# Sheet1.net
KiCad netlist of a schematic drawn in Altium Designer
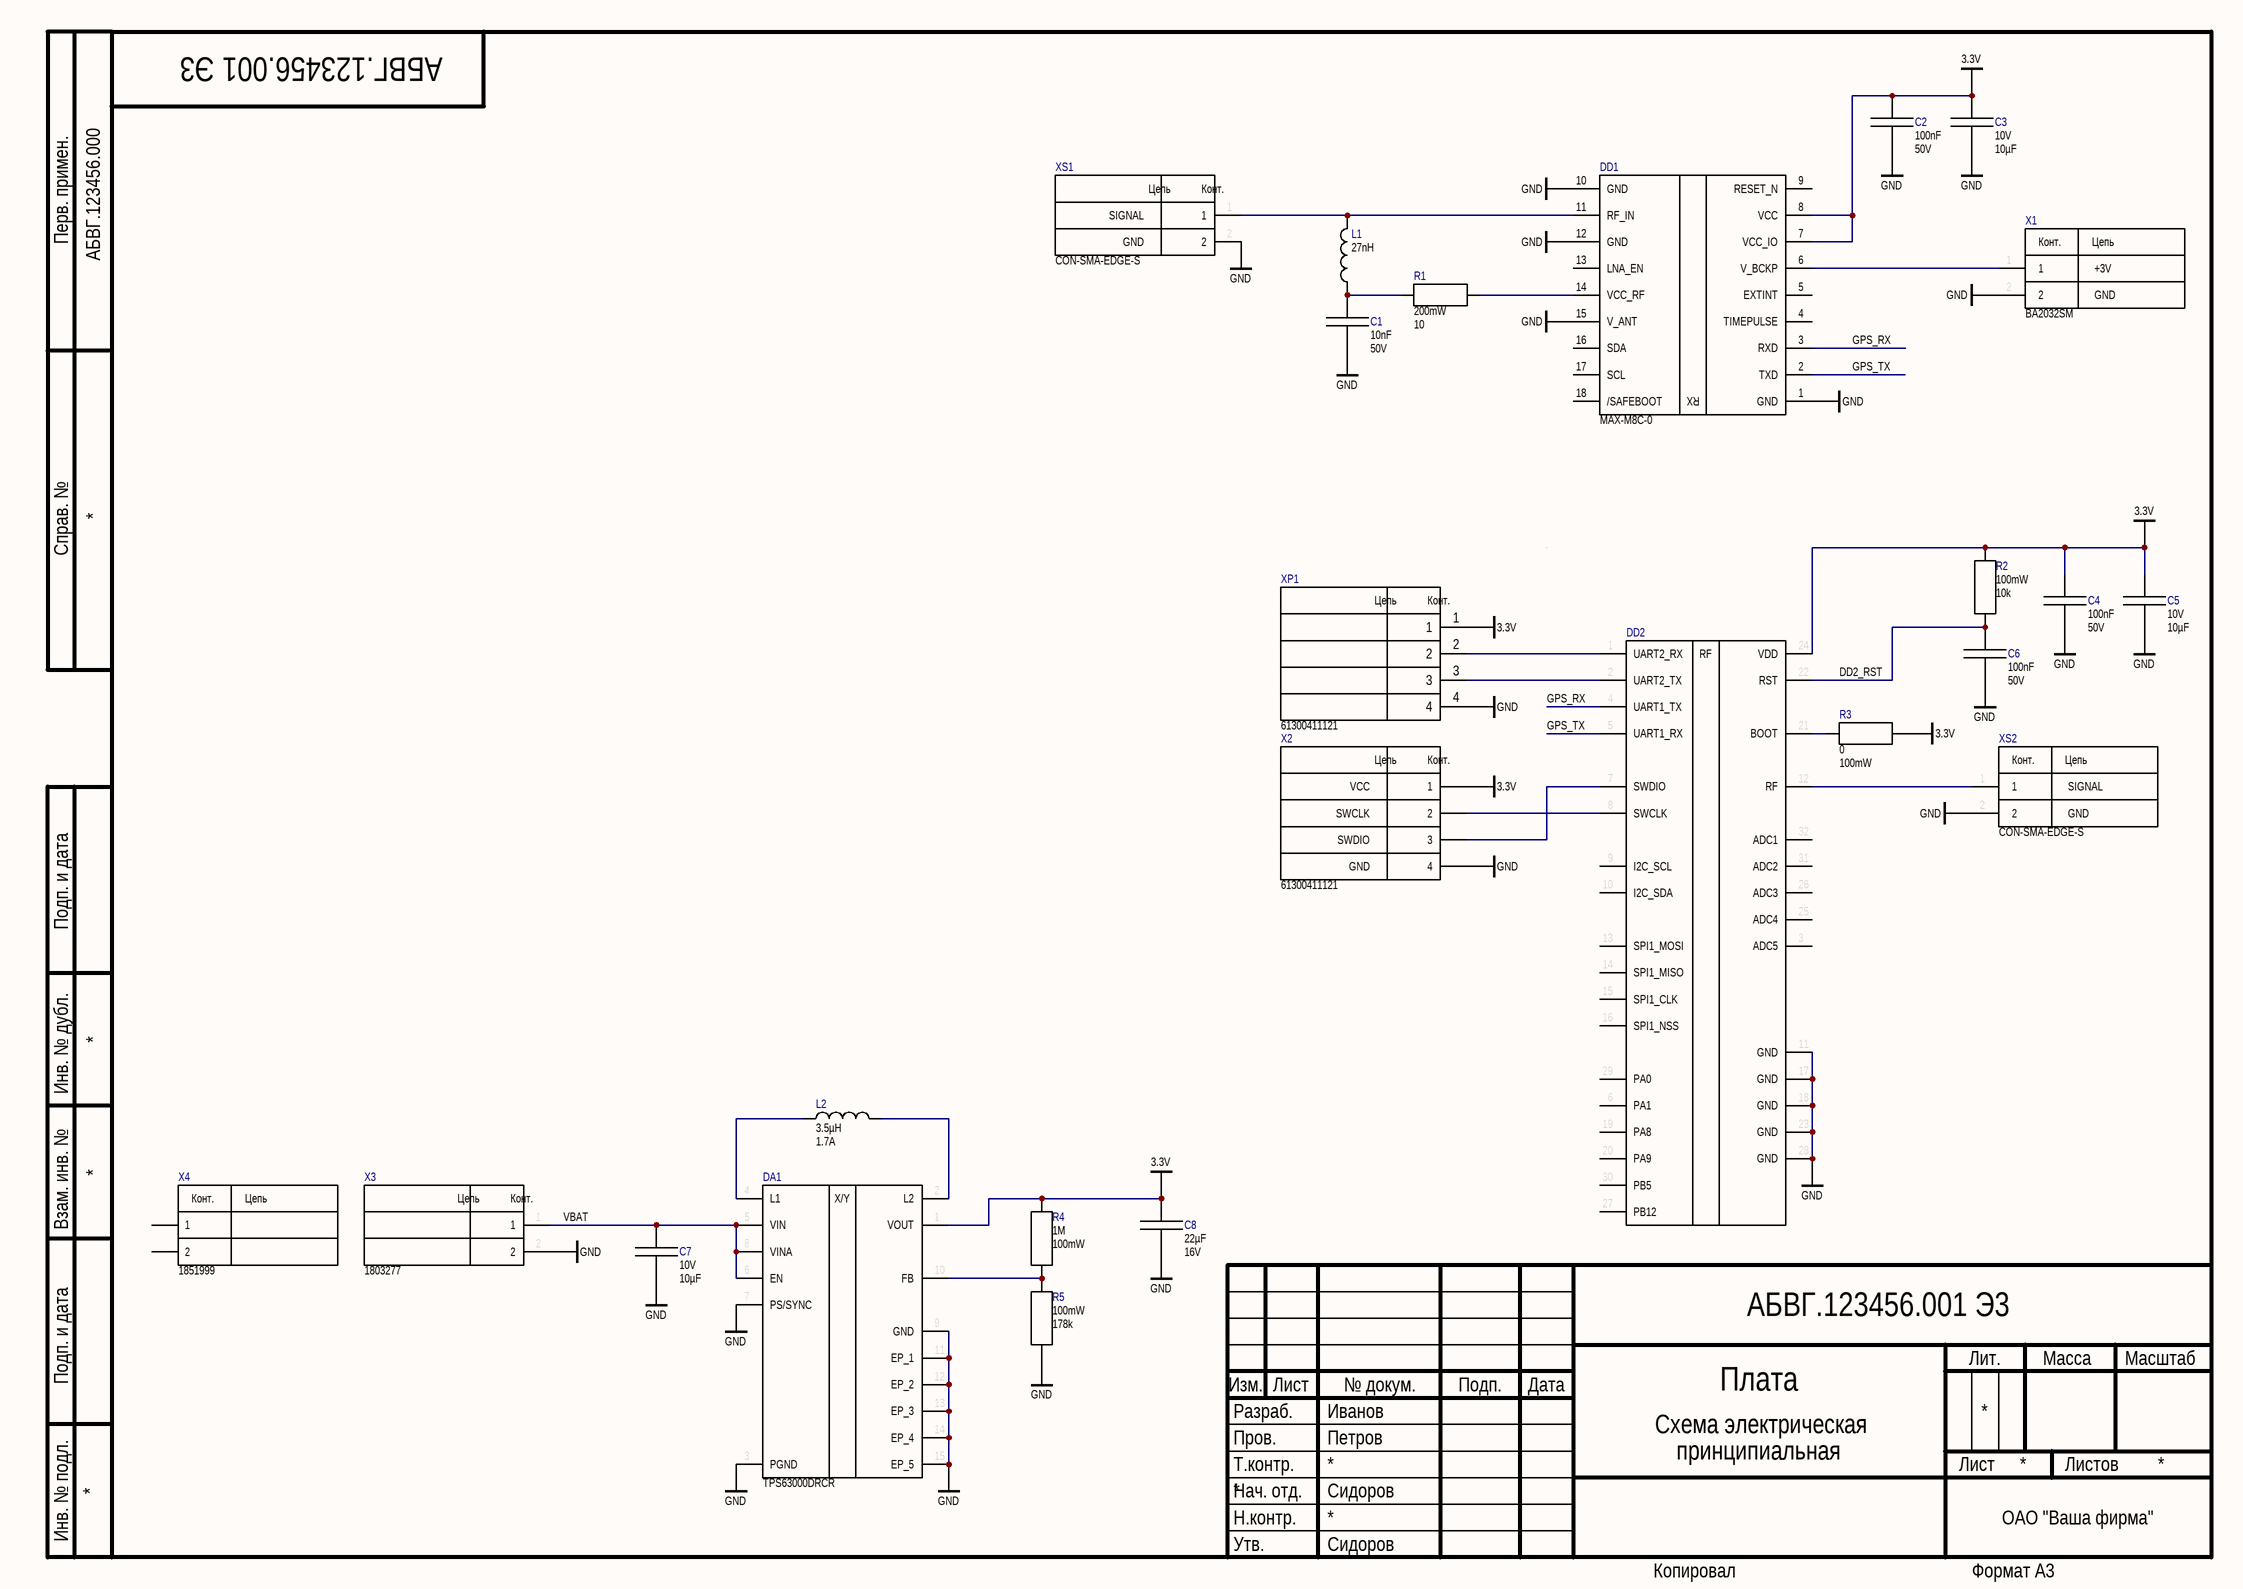
[diagram p0: Sheet1.SchDoc]

(export (version "E")
  (design (tool "Eeschema 10.0.6"))
  (components
    (comp (ref "C1")
      (value "10nF")
      (footprint "CAPC1608X09N")
      (description "CAP CER 10000PF 50V X7R 0603")
      (fields
        (field (name "VOLTAGE") "50V")
        (field (name "MANUFACTURER") "Murata")
        (field (name "VOLTAGE RATING") "50V")
        (field (name "SOURCE") "Meteo_1.SCHLIB")
      )
      (libsource (lib "Sergek Concord Server") (part "CAP-NP-2"))
    )
    (comp (ref "C2")
      (value "100nF")
      (footprint "CAPC1608X09N")
      (description "CAP CER 0.1UF 50V X7R 0603")
      (fields
        (field (name "VOLTAGE RATING") "50V")
        (field (name "TOLERANCE") "10%")
        (field (name "MANUFACTURER PART NUMBER") "GCM188R71H104KA57D")
        (field (name "SOURCE") "Meteo_1.SCHLIB")
      )
      (libsource (lib "Sergek Concord Server") (part "CAP-NP-2"))
    )
    (comp (ref "C3")
      (value "CL21Y106KPQVPNE")
      (footprint "CAPC2013X135X45NL10T25")
      (description "CAP CER 10UF 10V X7S 0805")
      (fields
        (field (name "MANUFACTURER") "Samsung")
        (field (name "VOLTAGE RATING") "10V")
        (field (name "CAPACITANCE") "10µF")
        (field (name "TOLERANCE") "10%")
      )
      (libsource (lib "Sergek Concord Server") (part "CAP-NP-2"))
    )
    (comp (ref "C4")
      (value "100nF")
      (footprint "CAPC1608X09N")
      (description "CAP CER 0.1UF 50V X7R 0603")
      (fields
        (field (name "VOLTAGE RATING") "50V")
        (field (name "TOLERANCE") "10%")
        (field (name "MANUFACTURER PART NUMBER") "GCM188R71H104KA57D")
        (field (name "SOURCE") "Meteo_1.SCHLIB")
      )
      (libsource (lib "Sergek Concord Server") (part "CAP-NP-2"))
    )
    (comp (ref "C5")
      (value "CL21Y106KPQVPNE")
      (footprint "CAPC2013X135X45NL10T25")
      (description "CAP CER 10UF 10V X7S 0805")
      (fields
        (field (name "MANUFACTURER") "Samsung")
        (field (name "VOLTAGE RATING") "10V")
        (field (name "CAPACITANCE") "10µF")
        (field (name "TOLERANCE") "10%")
      )
      (libsource (lib "Sergek Concord Server") (part "CAP-NP-2"))
    )
    (comp (ref "C6")
      (value "100nF")
      (footprint "CAPC1608X09N")
      (description "CAP CER 0.1UF 50V X7R 0603")
      (fields
        (field (name "VOLTAGE RATING") "50V")
        (field (name "TOLERANCE") "10%")
        (field (name "MANUFACTURER PART NUMBER") "GCM188R71H104KA57D")
        (field (name "SOURCE") "Meteo_1.SCHLIB")
      )
      (libsource (lib "Sergek Concord Server") (part "CAP-NP-2"))
    )
    (comp (ref "C7")
      (value "CL21Y106KPQVPNE")
      (footprint "CAPC2013X135X45NL10T25")
      (description "CAP CER 10UF 10V X7S 0805")
      (fields
        (field (name "MANUFACTURER") "Samsung")
        (field (name "VOLTAGE RATING") "10V")
        (field (name "CAPACITANCE") "10µF")
        (field (name "TOLERANCE") "10%")
      )
      (libsource (lib "Sergek Concord Server") (part "CAP-NP-2"))
    )
    (comp (ref "C8")
      (value "22µF")
      (footprint "CAPC2013X140X45NL15T25")
      (fields
        (field (name "VOLTAGE RATING") "16V")
        (field (name "TOLERANCE") "10%")
        (field (name "MANUFACTURER PART NUMBER") "C2012X5R1C226K125AC")
        (field (name "MANUFACTURER") "TDK")
      )
      (libsource (lib "Sergek Concord Server") (part "CAP-NP-2"))
    )
    (comp (ref "DA1")
      (value "TPS63000IDRCRQ1")
      (footprint "TPS63002DRCR")
      (description "IC REG BUCK BOOST ADJ 1.6A 10SON")
      (fields
        (field (name "MANUFACTURER PART NUMBER") "TPS63000DRCR")
        (field (name "MANUFACTURER") "Texas Instruments")
      )
      (libsource (lib "Sergek Concord Server") (part "TPS63000"))
    )
    (comp (ref "DD1")
      (value "MAX-M8C-0")
      (footprint "MAXM8C0")
      (description "IC Receiver Gps/gnss 18LCC")
      (fields (field (name "MANUFACTURER") "u-blox") (field (name "MANUFACTURER PART NUMBER") "MAX-M8C-0"))
      (libsource (lib "Sergek Concord Server") (part "MAX-M8C-0"))
    )
    (comp (ref "DD2")
      (value "RAK3172(H)")
      (footprint "RAK3172(H)-Footprint-1")
      (description "RAK3172 WisDuo LPWAN Module")
      (fields (field (name "MANUFACTURER") "RAK Wireless"))
      (libsource (lib "Sergek Concord Server") (part "RAK3172(H)"))
    )
    (comp (ref "L1")
      (value "27nH")
      (footprint "INDC1005X55X25ML5T10")
      (description "INDUCTOR")
      (fields (field (name "TOLERANCE") "2%") (field (name "MANUFACTURER PART NUMBER") "LQW15AN27NG00D"))
      (libsource (lib "Sergek Concord Server") (part "IND-2"))
    )
    (comp (ref "L2")
      (value "3.5µH")
      (footprint "SRU5018680Y")
      (description "Ind Power Shielded Wirewound 3.5uH 30% 100KHz 9Q-Factor Ferrite 2.1A T/R")
      (fields
        (field (name "TOLERANCE") "30%")
        (field (name "SATURATION CURRENT") "1.7A")
        (field (name "MANUFACTURER") "Bourns")
      )
      (libsource (lib "Sergek Concord Server") (part "IND-2"))
    )
    (comp (ref "R1")
      (value "10")
      (footprint "RESC1608X95X40LL15T20")
      (description "Thick Film Resistors - SMD 0.2W 10ohm 5% 100ppm Anti-Pulse")
      (fields
        (field (name "TOLERANCE") "5%")
        (field (name "POWER RATING") "200mW")
        (field (name "Comment") "SG73P1JTTD100J")
      )
      (libsource (lib "") (part "RES-2_1"))
    )
    (comp (ref "R2")
      (value "RMCF0603FT10K0")
      (footprint "RESC1608X55X25LL10T15")
      (description "RES SMD 10K OHM 1% 1/10W 0603")
      (fields
        (field (name "MANUFACTURER") "Stackpole Electronics Inc")
        (field (name "POWER RATING") "100mW")
        (field (name "RESISTANCE") "10k")
        (field (name "TOLERANCE") "1%")
      )
      (libsource (lib "Sergek Concord Server") (part "RES-2"))
    )
    (comp (ref "R3")
      (value "0")
      (footprint "RESC1608X55X25LL10T15")
      (description "Res Thkflm 0603 0 Ohm Jumper 1/10W 100Ppm/ C Smd Rohs Compliant: Yes")
      (fields
        (field (name "MANUFACTURER") "Stackpole Electronics Inc")
        (field (name "POWER RATING") "100mW")
        (field (name "MANUFACTURER PART NUMBER") "RMCF0603ZT0R00")
      )
      (libsource (lib "") (part "RES-2_1"))
    )
    (comp (ref "R4")
      (value "1M")
      (footprint "RESC1608X95X40LL15T20")
      (description "RES 1M OHM 5% 1/10W 0603")
      (fields
        (field (name "POWER RATING") "100mW")
        (field (name "TOLERANCE") "5%")
        (field (name "MANUFACTURER PART NUMBER") "RMCF0603JT1M00")
      )
      (libsource (lib "Sergek Concord Server") (part "RES-2"))
    )
    (comp (ref "R5")
      (value "178k")
      (footprint "RESC1608X95X40LL15T20")
      (fields
        (field (name "TOLERANCE") "1%")
        (field (name "POWER RATING") "100mW")
        (field (name "MANUFACTURER PART NUMBER") "ERJ-3EKF1783V")
        (field (name "MANUFACTURER") "Panasonic")
      )
      (libsource (lib "Sergek Concord Server") (part "RES-2"))
    )
    (comp (ref "X1")
      (value "BA2032SM")
      (footprint "MPD-BA2032SM_V")
      (description "Battery Holder Coin 20MM SMD")
      (fields
        (field (name "MANUFACTURER") "Memory Protection Devices")
        (field (name "MANUFACTURER PART NUMBER") "BA2032SM")
      )
      (libsource (lib "Sergek Concord Server") (part "BATTERY-HOLDER-COIN-2"))
    )
    (comp (ref "X2")
      (value "ST-LINK-SWD-CONNECTOR")
      (footprint "20021311-00010T4LF-Footprint-1")
      (description "Conn Unshrouded Header HDR 4 POS 2.54mm Solder ST Thru-Hole Bag")
      (fields
        (field (name "MANUFACTURER PART NUMBER") "61300411121")
        (field (name "MANUFACTURER") "Würth Elektronik")
      )
      (libsource (lib "Sergek Concord Server") (part "ST-LINK-SWD"))
    )
    (comp (ref "X3")
      (value "1803277")
      (footprint "PHOE-1803277_V")
      (description "Male Header, Pitch 3.81 mm, 1 x 2 Position, Height 7.25 mm, Tail Length 3.4 mm, RoHS, Bulk")
      (fields
        (field (name "MANUFACTURER") "Phoenix Contact")
        (field (name "MANUFACTURER PART NUMBER") "1803277")
      )
      (libsource (lib "Sergek Concord Server") (part "CN-1P-M-R2"))
    )
    (comp (ref "X4")
      (value "1851999")
      (description "Pluggable Terminal Blocks 2 Pos 3.81mm pitch Plug 28-16 AWG Screw")
      (fields
        (field (name "MANUFACTURER PART NUMBER") "1851999")
        (field (name "VOLTAGE") "300V")
        (field (name "MANUFACTURER") "Phoenix Contact")
      )
      (libsource (lib "Sergek Concord Server") (part "X-2"))
    )
    (comp (ref "XP1")
      (value "61300411121")
      (footprint "20021311-00010T4LF-Footprint-1")
      (description "Conn Unshrouded Header HDR 4 POS 2.54mm Solder ST Thru-Hole Bag")
      (fields
        (field (name "MANUFACTURER") "Würth Elektronik")
        (field (name "MANUFACTURER PART NUMBER") "61300411121")
      )
      (libsource (lib "Sergek Concord Server") (part "XP-4"))
    )
    (comp (ref "XS1")
      (value "CON-SMA-EDGE-S")
      (footprint "RFSOLUTIONS_CON-SMA-EDGE-S")
      (description "CONN SMA JACK STR EDGE MNT")
      (fields
        (field (name "MANUFACTURER PART NUMBER") "CON-SMA-EDGE-S")
        (field (name "MANUFACTURER") "RF Solutions")
      )
      (libsource (lib "Sergek Concord Server") (part "CON-SMA-EDGE-S"))
    )
    (comp (ref "XS2")
      (value "CON-SMA-EDGE-S")
      (footprint "RFSOLUTIONS_CON-SMA-EDGE-S")
      (description "CONN SMA JACK STR EDGE MNT")
      (fields
        (field (name "MANUFACTURER PART NUMBER") "CON-SMA-EDGE-S")
        (field (name "MANUFACTURER") "RF Solutions")
      )
      (libsource (lib "") (part "CON-SMA-EDGE-S_1"))
    )
  )
  (nets
    (net (code "1") (name "/DD2_RST") (class "Default")
      (node (ref "C6") (pin "2") (pinfunction "2_2") (pintype "passive"))
      (node (ref "DD2") (pin "22") (pinfunction "RST_22") (pintype "passive"))
      (node (ref "R2") (pin "1") (pinfunction "1_1") (pintype "passive"))
    )
    (net (code "2") (name "/GPS_RX") (class "Default")
      (node (ref "DD1") (pin "3") (pinfunction "RXD_3") (pintype "passive"))
      (node (ref "DD2") (pin "4") (pinfunction "UART1_TX_4") (pintype "passive"))
    )
    (net (code "3") (name "/GPS_TX") (class "Default")
      (node (ref "DD1") (pin "2") (pinfunction "TXD_2") (pintype "passive"))
      (node (ref "DD2") (pin "5") (pinfunction "UART1_RX_5") (pintype "passive"))
    )
    (net (code "4") (name "/VBAT") (class "Default")
      (node (ref "C7") (pin "2") (pinfunction "2_2") (pintype "passive"))
      (node (ref "DA1") (pin "5") (pinfunction "VIN_5") (pintype "passive"))
      (node (ref "DA1") (pin "6") (pinfunction "EN_6") (pintype "passive"))
      (node (ref "DA1") (pin "8") (pinfunction "VINA_8") (pintype "passive"))
      (node (ref "X3") (pin "1") (pinfunction "1_1") (pintype "passive"))
    )
    (net (code "5") (name "3.3V") (class "Default")
      (node (ref "C2") (pin "1") (pinfunction "1_1") (pintype "passive"))
      (node (ref "C3") (pin "2") (pinfunction "2_2") (pintype "passive"))
      (node (ref "C4") (pin "2") (pinfunction "2_2") (pintype "passive"))
      (node (ref "C5") (pin "2") (pinfunction "2_2") (pintype "passive"))
      (node (ref "C8") (pin "2") (pinfunction "2_2") (pintype "passive"))
      (node (ref "DA1") (pin "1") (pinfunction "VOUT_1") (pintype "passive"))
      (node (ref "DD1") (pin "7") (pinfunction "VCC_IO_7") (pintype "passive"))
      (node (ref "DD1") (pin "8") (pinfunction "VCC_8") (pintype "passive"))
      (node (ref "DD2") (pin "24") (pinfunction "VDD_24") (pintype "passive"))
      (node (ref "R2") (pin "2") (pinfunction "2_2") (pintype "passive"))
      (node (ref "R3") (pin "2") (pinfunction "2_2") (pintype "passive"))
      (node (ref "R4") (pin "2") (pinfunction "2_2") (pintype "passive"))
      (node (ref "X2") (pin "1") (pinfunction "VCC_1") (pintype "passive"))
      (node (ref "XP1") (pin "1") (pinfunction "1_1") (pintype "passive"))
    )
    (net (code "6") (name "GND") (class "Default")
      (node (ref "C1") (pin "2") (pinfunction "2_2") (pintype "passive"))
      (node (ref "C2") (pin "2") (pinfunction "2_2") (pintype "passive"))
      (node (ref "C3") (pin "1") (pinfunction "1_1") (pintype "passive"))
      (node (ref "C4") (pin "1") (pinfunction "1_1") (pintype "passive"))
      (node (ref "C5") (pin "1") (pinfunction "1_1") (pintype "passive"))
      (node (ref "C6") (pin "1") (pinfunction "1_1") (pintype "passive"))
      (node (ref "C7") (pin "1") (pinfunction "1_1") (pintype "passive"))
      (node (ref "C8") (pin "1") (pinfunction "1_1") (pintype "passive"))
      (node (ref "DA1") (pin "11") (pinfunction "EP_1_11") (pintype "passive"))
      (node (ref "DA1") (pin "12") (pinfunction "EP_2_12") (pintype "passive"))
      (node (ref "DA1") (pin "13") (pinfunction "EP_3_13") (pintype "passive"))
      (node (ref "DA1") (pin "14") (pinfunction "EP_4_14") (pintype "passive"))
      (node (ref "DA1") (pin "15") (pinfunction "EP_5_15") (pintype "passive"))
      (node (ref "DA1") (pin "3") (pinfunction "PGND_3") (pintype "passive"))
      (node (ref "DA1") (pin "7") (pinfunction "PS/SYNC_7") (pintype "passive"))
      (node (ref "DA1") (pin "9") (pinfunction "GND_9") (pintype "passive"))
      (node (ref "DD1") (pin "1") (pinfunction "GND_1") (pintype "passive"))
      (node (ref "DD1") (pin "10") (pinfunction "GND_10") (pintype "passive"))
      (node (ref "DD1") (pin "12") (pinfunction "GND_12") (pintype "passive"))
      (node (ref "DD1") (pin "15") (pinfunction "V_ANT_15") (pintype "passive"))
      (node (ref "DD2") (pin "11") (pinfunction "GND_11") (pintype "passive"))
      (node (ref "DD2") (pin "17") (pinfunction "GND_17") (pintype "passive"))
      (node (ref "DD2") (pin "18") (pinfunction "GND_18") (pintype "passive"))
      (node (ref "DD2") (pin "23") (pinfunction "GND_23") (pintype "passive"))
      (node (ref "DD2") (pin "28") (pinfunction "GND_28") (pintype "passive"))
      (node (ref "R5") (pin "1") (pinfunction "1_1") (pintype "passive"))
      (node (ref "X1") (pin "2") (pinfunction "GND_2") (pintype "passive"))
      (node (ref "X2") (pin "4") (pinfunction "GND_4") (pintype "passive"))
      (node (ref "X3") (pin "2") (pinfunction "2_2") (pintype "passive"))
      (node (ref "XP1") (pin "4") (pinfunction "4_4") (pintype "passive"))
      (node (ref "XS1") (pin "2") (pinfunction "GND_2") (pintype "passive"))
      (node (ref "XS2") (pin "2") (pinfunction "GND_2") (pintype "passive"))
    )
    (net (code "7") (name "Net-(C1-Pad1)") (class "Default")
      (node (ref "C1") (pin "1") (pinfunction "1_1") (pintype "passive"))
      (node (ref "L1") (pin "1") (pinfunction "1_1") (pintype "passive"))
      (node (ref "R1") (pin "1") (pinfunction "1_1") (pintype "passive"))
    )
    (net (code "8") (name "Net-(DA1-FB)") (class "Default")
      (node (ref "DA1") (pin "10") (pinfunction "FB_10") (pintype "passive"))
      (node (ref "R4") (pin "1") (pinfunction "1_1") (pintype "passive"))
      (node (ref "R5") (pin "2") (pinfunction "2_2") (pintype "passive"))
    )
    (net (code "9") (name "Net-(DA1-L1)") (class "Default")
      (node (ref "DA1") (pin "4") (pinfunction "L1_4") (pintype "passive"))
      (node (ref "L2") (pin "1") (pinfunction "1_1") (pintype "passive"))
    )
    (net (code "10") (name "Net-(DA1-L2)") (class "Default")
      (node (ref "DA1") (pin "2") (pinfunction "L2_2") (pintype "passive"))
      (node (ref "L2") (pin "2") (pinfunction "2_2") (pintype "passive"))
    )
    (net (code "11") (name "Net-(DD1-RF_IN)") (class "Default")
      (node (ref "DD1") (pin "11") (pinfunction "RF_IN_11") (pintype "passive"))
      (node (ref "L1") (pin "2") (pinfunction "2_2") (pintype "passive"))
      (node (ref "XS1") (pin "1") (pinfunction "SIGNAL_1") (pintype "passive"))
    )
    (net (code "12") (name "Net-(DD1-VCC_RF)") (class "Default")
      (node (ref "DD1") (pin "14") (pinfunction "VCC_RF_14") (pintype "passive"))
      (node (ref "R1") (pin "2") (pinfunction "2_2") (pintype "passive"))
    )
    (net (code "13") (name "Net-(DD1-V_BCKP)") (class "Default")
      (node (ref "DD1") (pin "6") (pinfunction "V_BCKP_6") (pintype "passive"))
      (node (ref "X1") (pin "1") (pinfunction "+3V_1") (pintype "passive"))
    )
    (net (code "14") (name "Net-(DD2-BOOT)") (class "Default")
      (node (ref "DD2") (pin "21") (pinfunction "BOOT_21") (pintype "passive"))
      (node (ref "R3") (pin "1") (pinfunction "1_1") (pintype "passive"))
    )
    (net (code "15") (name "Net-(DD2-RF)") (class "Default")
      (node (ref "DD2") (pin "12") (pinfunction "RF_12") (pintype "passive"))
      (node (ref "XS2") (pin "1") (pinfunction "SIGNAL_1") (pintype "passive"))
    )
    (net (code "16") (name "Net-(DD2-SWCLK)") (class "Default")
      (node (ref "DD2") (pin "8") (pinfunction "SWCLK_8") (pintype "passive"))
      (node (ref "X2") (pin "2") (pinfunction "SWCLK_2") (pintype "passive"))
    )
    (net (code "17") (name "Net-(DD2-SWDIO)") (class "Default")
      (node (ref "DD2") (pin "7") (pinfunction "SWDIO_7") (pintype "passive"))
      (node (ref "X2") (pin "3") (pinfunction "SWDIO_3") (pintype "passive"))
    )
    (net (code "18") (name "Net-(DD2-UART2_RX)") (class "Default")
      (node (ref "DD2") (pin "1") (pinfunction "UART2_RX_1") (pintype "passive"))
      (node (ref "XP1") (pin "2") (pinfunction "2_2") (pintype "passive"))
    )
    (net (code "19") (name "Net-(DD2-UART2_TX)") (class "Default")
      (node (ref "DD2") (pin "2") (pinfunction "UART2_TX_2") (pintype "passive"))
      (node (ref "XP1") (pin "3") (pinfunction "3_3") (pintype "passive"))
    )
    (net (code "20") (name "unconnected-(DD1-EXTINT-Pad5)") (class "Default")
      (node (ref "DD1") (pin "5") (pinfunction "EXTINT_5") (pintype "passive"))
    )
    (net (code "21") (name "unconnected-(DD1-LNA_EN-Pad13)") (class "Default")
      (node (ref "DD1") (pin "13") (pinfunction "LNA_EN_13") (pintype "passive"))
    )
    (net (code "22") (name "unconnected-(DD1-RESET_N-Pad9)") (class "Default")
      (node (ref "DD1") (pin "9") (pinfunction "RESET_N_9") (pintype "passive"))
    )
    (net (code "23") (name "unconnected-(DD1-SCL-Pad17)") (class "Default")
      (node (ref "DD1") (pin "17") (pinfunction "SCL_17") (pintype "passive"))
    )
    (net (code "24") (name "unconnected-(DD1-SDA-Pad16)") (class "Default")
      (node (ref "DD1") (pin "16") (pinfunction "SDA_16") (pintype "passive"))
    )
    (net (code "25") (name "unconnected-(DD1-TIMEPULSE-Pad4)") (class "Default")
      (node (ref "DD1") (pin "4") (pinfunction "TIMEPULSE_4") (pintype "passive"))
    )
    (net (code "26") (name "unconnected-(DD1-{slash}SAFEBOOT-Pad18)") (class "Default")
      (node (ref "DD1") (pin "18") (pinfunction "/SAFEBOOT_18") (pintype "passive"))
    )
    (net (code "27") (name "unconnected-(DD2-ADC1-Pad32)") (class "Default")
      (node (ref "DD2") (pin "32") (pinfunction "ADC1_32") (pintype "passive"))
    )
    (net (code "28") (name "unconnected-(DD2-ADC2-Pad31)") (class "Default")
      (node (ref "DD2") (pin "31") (pinfunction "ADC2_31") (pintype "passive"))
    )
    (net (code "29") (name "unconnected-(DD2-ADC3-Pad26)") (class "Default")
      (node (ref "DD2") (pin "26") (pinfunction "ADC3_26") (pintype "passive"))
    )
    (net (code "30") (name "unconnected-(DD2-ADC4-Pad25)") (class "Default")
      (node (ref "DD2") (pin "25") (pinfunction "ADC4_25") (pintype "passive"))
    )
    (net (code "31") (name "unconnected-(DD2-ADC5-Pad3)") (class "Default")
      (node (ref "DD2") (pin "3") (pinfunction "ADC5_3") (pintype "passive"))
    )
    (net (code "32") (name "unconnected-(DD2-I2C_SCL-Pad9)") (class "Default")
      (node (ref "DD2") (pin "9") (pinfunction "I2C_SCL_9") (pintype "passive"))
    )
    (net (code "33") (name "unconnected-(DD2-I2C_SDA-Pad10)") (class "Default")
      (node (ref "DD2") (pin "10") (pinfunction "I2C_SDA_10") (pintype "passive"))
    )
    (net (code "34") (name "unconnected-(DD2-PA0-Pad29)") (class "Default")
      (node (ref "DD2") (pin "29") (pinfunction "PA0_29") (pintype "passive"))
    )
    (net (code "35") (name "unconnected-(DD2-PA1-Pad6)") (class "Default")
      (node (ref "DD2") (pin "6") (pinfunction "PA1_6") (pintype "passive"))
    )
    (net (code "36") (name "unconnected-(DD2-PA8-Pad19)") (class "Default")
      (node (ref "DD2") (pin "19") (pinfunction "PA8_19") (pintype "passive"))
    )
    (net (code "37") (name "unconnected-(DD2-PA9-Pad20)") (class "Default")
      (node (ref "DD2") (pin "20") (pinfunction "PA9_20") (pintype "passive"))
    )
    (net (code "38") (name "unconnected-(DD2-PB5-Pad30)") (class "Default")
      (node (ref "DD2") (pin "30") (pinfunction "PB5_30") (pintype "passive"))
    )
    (net (code "39") (name "unconnected-(DD2-PB12-Pad27)") (class "Default")
      (node (ref "DD2") (pin "27") (pinfunction "PB12_27") (pintype "passive"))
    )
    (net (code "40") (name "unconnected-(DD2-SPI1_CLK-Pad15)") (class "Default")
      (node (ref "DD2") (pin "15") (pinfunction "SPI1_CLK_15") (pintype "passive"))
    )
    (net (code "41") (name "unconnected-(DD2-SPI1_MISO-Pad14)") (class "Default")
      (node (ref "DD2") (pin "14") (pinfunction "SPI1_MISO_14") (pintype "passive"))
    )
    (net (code "42") (name "unconnected-(DD2-SPI1_MOSI-Pad13)") (class "Default")
      (node (ref "DD2") (pin "13") (pinfunction "SPI1_MOSI_13") (pintype "passive"))
    )
    (net (code "43") (name "unconnected-(DD2-SPI1_NSS-Pad16)") (class "Default")
      (node (ref "DD2") (pin "16") (pinfunction "SPI1_NSS_16") (pintype "passive"))
    )
    (net (code "44") (name "unconnected-(X4-Pad1)") (class "Default")
      (node (ref "X4") (pin "1") (pinfunction "1_1") (pintype "passive"))
    )
    (net (code "45") (name "unconnected-(X4-Pad2)") (class "Default")
      (node (ref "X4") (pin "2") (pinfunction "2_2") (pintype "passive"))
    )
  )
)
